# support.net
KiCad netlist of a schematic drawn in Altium Designer
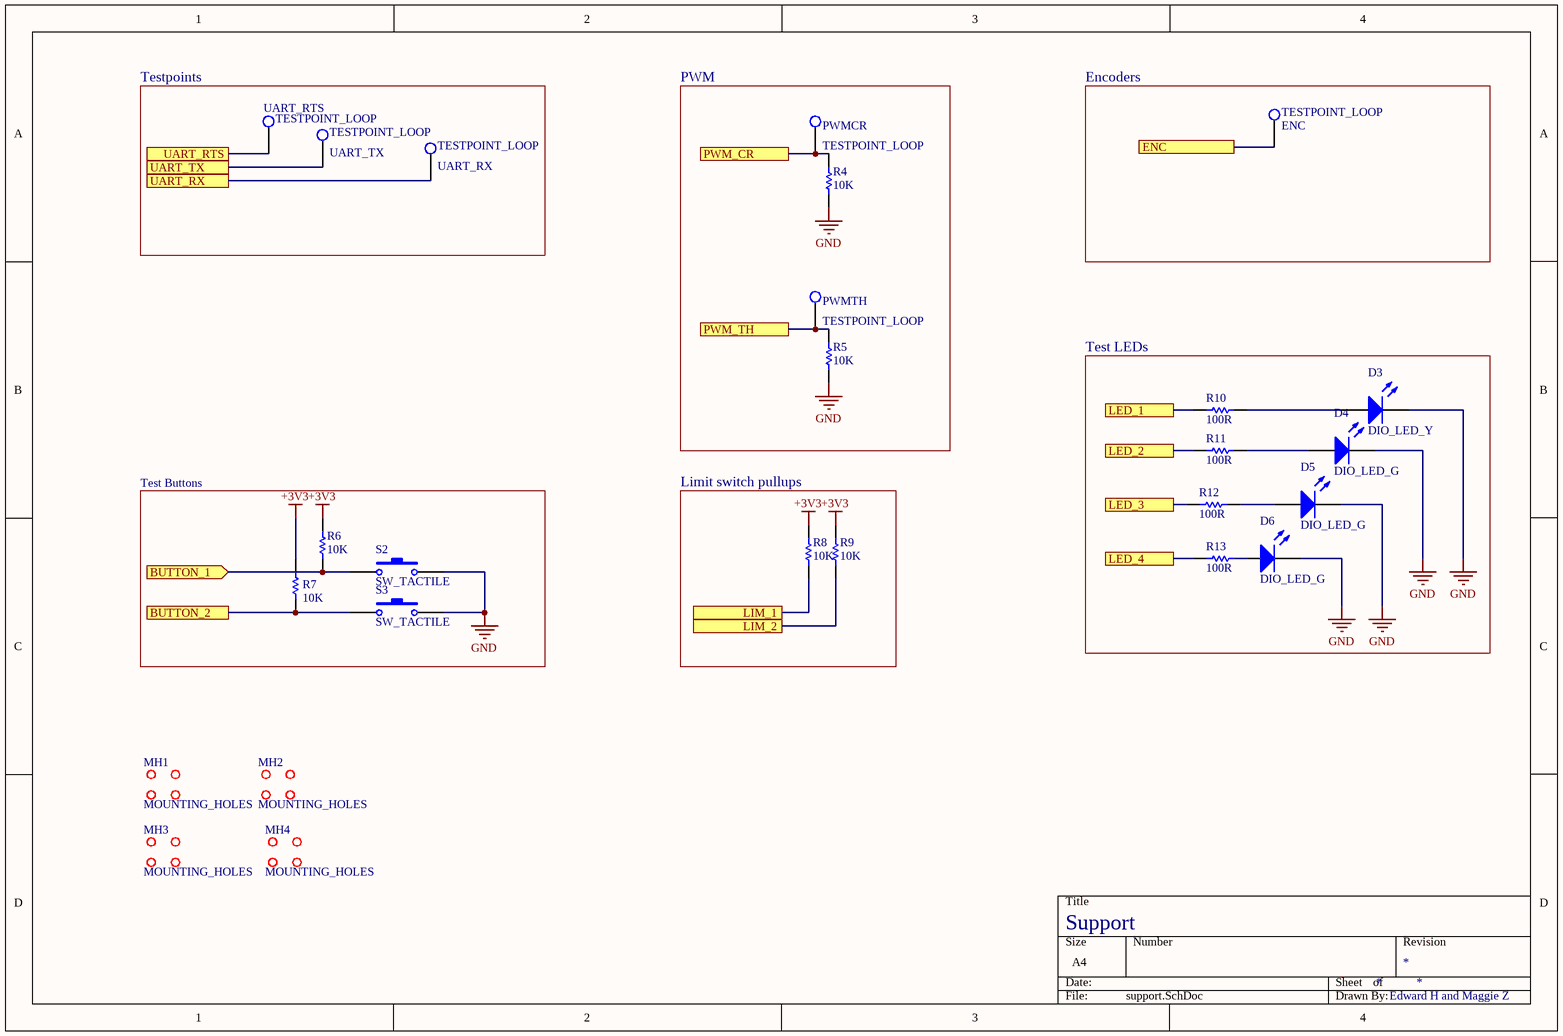
[diagram p0: support.SchDoc]

(export (version "E")
  (design (tool "Eeschema 10.0.6"))
  (components
    (comp (ref "D3")
      (value "DIO_LED_Y")
      (footprint "LED_0805_LINE")
      (description "LED YELLOW DIFFUSED 0805 SMD")
      (fields (field (name "MANUFACTURER") "OSRAM") (field (name "MPN") "LY R976-PS-36"))
      (libsource (lib "UWRT_Schematic_Library_2019") (part "DIO_LED_Y"))
    )
    (comp (ref "D4")
      (value "DIO_LED_G")
      (footprint "LED_0805_LINE")
      (description "LED GREEN DIFFUSED 0805 SMD")
      (fields (field (name "MANUFACTURER") "OSRAM") (field (name "MPN") "LG R971-KN-1"))
      (libsource (lib "UWRT_Schematic_Library_2019") (part "DIO_LED_G"))
    )
    (comp (ref "D5")
      (value "DIO_LED_G")
      (footprint "LED_0805_LINE")
      (description "LED GREEN DIFFUSED 0805 SMD")
      (fields (field (name "MANUFACTURER") "OSRAM") (field (name "MPN") "LG R971-KN-1"))
      (libsource (lib "UWRT_Schematic_Library_2019") (part "DIO_LED_G"))
    )
    (comp (ref "D6")
      (value "DIO_LED_G")
      (footprint "LED_0805_LINE")
      (description "LED GREEN DIFFUSED 0805 SMD")
      (fields (field (name "MANUFACTURER") "OSRAM") (field (name "MPN") "LG R971-KN-1"))
      (libsource (lib "UWRT_Schematic_Library_2019") (part "DIO_LED_G"))
    )
    (comp (ref "ENC")
      (value "TESTPOINT_LOOP")
      (footprint "TESTPOINT_LOOP")
      (libsource (lib "UWRT_Schematic_Library_2019") (part "TESTPOINT_LOOP"))
    )
    (comp (ref "MH1")
      (value "MOUNTING_HOLES")
      (footprint "MOUNTING_HOLE")
      (description "6cm x 6cm")
      (libsource (lib "UWRT_Schematic_Library_2019") (part "MOUNTING_HOLES"))
    )
    (comp (ref "MH2")
      (value "MOUNTING_HOLES")
      (footprint "MOUNTING_HOLE")
      (description "6cm x 6cm")
      (libsource (lib "UWRT_Schematic_Library_2019") (part "MOUNTING_HOLES"))
    )
    (comp (ref "MH3")
      (value "MOUNTING_HOLES")
      (footprint "MOUNTING_HOLE")
      (description "6cm x 6cm")
      (libsource (lib "UWRT_Schematic_Library_2019") (part "MOUNTING_HOLES"))
    )
    (comp (ref "MH4")
      (value "MOUNTING_HOLES")
      (footprint "MOUNTING_HOLE")
      (description "6cm x 6cm")
      (libsource (lib "UWRT_Schematic_Library_2019") (part "MOUNTING_HOLES"))
    )
    (comp (ref "PWMCR")
      (value "TESTPOINT_LOOP")
      (footprint "TESTPOINT_LOOP")
      (libsource (lib "UWRT_Schematic_Library_2019") (part "TESTPOINT_LOOP"))
    )
    (comp (ref "PWMTH")
      (value "TESTPOINT_LOOP")
      (footprint "TESTPOINT_LOOP")
      (libsource (lib "UWRT_Schematic_Library_2019") (part "TESTPOINT_LOOP"))
    )
    (comp (ref "R4")
      (value "10K")
      (footprint "RESC0603(1608)_N")
      (description "RES SMD 10K OHM 5% 1/10W 0603")
      (fields (field (name "MANUFACTURER") "Yageo") (field (name "TOLERANCE") "5%"))
      (libsource (lib "UWRT_Schematic_Library_2019") (part "RES_10K_0603"))
    )
    (comp (ref "R5")
      (value "10K")
      (footprint "RESC0603(1608)_N")
      (description "RES SMD 10K OHM 5% 1/10W 0603")
      (fields (field (name "MANUFACTURER") "Yageo") (field (name "TOLERANCE") "5%"))
      (libsource (lib "UWRT_Schematic_Library_2019") (part "RES_10K_0603"))
    )
    (comp (ref "R6")
      (value "10K")
      (footprint "RESC0603(1608)_N")
      (description "RES SMD 10K OHM 5% 1/10W 0603")
      (fields (field (name "MANUFACTURER") "Yageo") (field (name "TOLERANCE") "5%"))
      (libsource (lib "UWRT_Schematic_Library_2019") (part "RES_10K_0603"))
    )
    (comp (ref "R7")
      (value "10K")
      (footprint "RESC0603(1608)_N")
      (description "RES SMD 10K OHM 5% 1/10W 0603")
      (fields (field (name "MANUFACTURER") "Yageo") (field (name "TOLERANCE") "5%"))
      (libsource (lib "UWRT_Schematic_Library_2019") (part "RES_10K_0603"))
    )
    (comp (ref "R8")
      (value "10K")
      (footprint "RESC0603(1608)_N")
      (description "RES SMD 10K OHM 5% 1/10W 0603")
      (fields (field (name "MANUFACTURER") "Yageo") (field (name "TOLERANCE") "5%"))
      (libsource (lib "UWRT_Schematic_Library_2019") (part "RES_10K_0603"))
    )
    (comp (ref "R9")
      (value "10K")
      (footprint "RESC0603(1608)_N")
      (description "RES SMD 10K OHM 5% 1/10W 0603")
      (fields (field (name "MANUFACTURER") "Yageo") (field (name "TOLERANCE") "5%"))
      (libsource (lib "UWRT_Schematic_Library_2019") (part "RES_10K_0603"))
    )
    (comp (ref "R10")
      (value "100R")
      (footprint "RESC0603(1608)_N")
      (description "RES SMD 100 OHM 1% 1/10W 0603")
      (fields (field (name "MANUFACTURER") "Yageo") (field (name "TOLERANCE") "1%"))
      (libsource (lib "UWRT_Schematic_Library_2019") (part "RES_100R_0603"))
    )
    (comp (ref "R11")
      (value "100R")
      (footprint "RESC0603(1608)_N")
      (description "RES SMD 100 OHM 1% 1/10W 0603")
      (fields (field (name "MANUFACTURER") "Yageo") (field (name "TOLERANCE") "1%"))
      (libsource (lib "UWRT_Schematic_Library_2019") (part "RES_100R_0603"))
    )
    (comp (ref "R12")
      (value "100R")
      (footprint "RESC0603(1608)_N")
      (description "RES SMD 100 OHM 1% 1/10W 0603")
      (fields (field (name "MANUFACTURER") "Yageo") (field (name "TOLERANCE") "1%"))
      (libsource (lib "UWRT_Schematic_Library_2019") (part "RES_100R_0603"))
    )
    (comp (ref "R13")
      (value "100R")
      (footprint "RESC0603(1608)_N")
      (description "RES SMD 100 OHM 1% 1/10W 0603")
      (fields (field (name "MANUFACTURER") "Yageo") (field (name "TOLERANCE") "1%"))
      (libsource (lib "UWRT_Schematic_Library_2019") (part "RES_100R_0603"))
    )
    (comp (ref "S2")
      (value "SW_TACTILE")
      (footprint "B3U-1100P")
      (description "Tactile Switch (Grey)")
      (fields (field (name "DIGIKEY PART NUMBER") "SW1021TR-ND") (field (name "MPN") "B3U-1100P"))
      (libsource (lib "UWRT_Schematic_Library_2019") (part "SW_TACTILE"))
    )
    (comp (ref "S3")
      (value "SW_TACTILE")
      (footprint "B3U-1100P")
      (description "Tactile Switch (Grey)")
      (fields (field (name "DIGIKEY PART NUMBER") "SW1021TR-ND") (field (name "MPN") "B3U-1100P"))
      (libsource (lib "UWRT_Schematic_Library_2019") (part "SW_TACTILE"))
    )
    (comp (ref "UART_RTS")
      (value "TESTPOINT_LOOP")
      (footprint "TESTPOINT_LOOP")
      (libsource (lib "UWRT_Schematic_Library_2019") (part "TESTPOINT_LOOP"))
    )
    (comp (ref "UART_RX")
      (value "TESTPOINT_LOOP")
      (footprint "TESTPOINT_LOOP")
      (libsource (lib "UWRT_Schematic_Library_2019") (part "TESTPOINT_LOOP"))
    )
    (comp (ref "UART_TX")
      (value "TESTPOINT_LOOP")
      (footprint "TESTPOINT_LOOP")
      (libsource (lib "UWRT_Schematic_Library_2019") (part "TESTPOINT_LOOP"))
    )
  )
  (nets
    (net (code "1") (name "+3V3") (class "Default")
      (node (ref "R6") (pin "2") (pinfunction "2_2") (pintype "passive"))
      (node (ref "R7") (pin "1") (pinfunction "1_1") (pintype "passive"))
      (node (ref "R8") (pin "2") (pinfunction "2_2") (pintype "passive"))
      (node (ref "R9") (pin "2") (pinfunction "2_2") (pintype "passive"))
    )
    (net (code "2") (name "/BUTTON_1") (class "Default")
      (node (ref "R6") (pin "1") (pinfunction "1_1") (pintype "passive"))
      (node (ref "S2") (pin "1") (pinfunction "1_1") (pintype "passive"))
    )
    (net (code "3") (name "/BUTTON_2") (class "Default")
      (node (ref "R7") (pin "2") (pinfunction "2_2") (pintype "passive"))
      (node (ref "S3") (pin "1") (pinfunction "1_1") (pintype "passive"))
    )
    (net (code "4") (name "/ENC") (class "Default")
      (node (ref "ENC") (pin "1") (pinfunction "=value_1") (pintype "passive"))
    )
    (net (code "5") (name "/LED_1") (class "Default")
      (node (ref "R10") (pin "2") (pinfunction "2_2") (pintype "passive"))
    )
    (net (code "6") (name "/LED_2") (class "Default")
      (node (ref "R11") (pin "2") (pinfunction "2_2") (pintype "passive"))
    )
    (net (code "7") (name "/LED_3") (class "Default")
      (node (ref "R12") (pin "2") (pinfunction "2_2") (pintype "passive"))
    )
    (net (code "8") (name "/LED_4") (class "Default")
      (node (ref "R13") (pin "2") (pinfunction "2_2") (pintype "passive"))
    )
    (net (code "9") (name "/LIM_1") (class "Default")
      (node (ref "R8") (pin "1") (pinfunction "1_1") (pintype "passive"))
    )
    (net (code "10") (name "/LIM_2") (class "Default")
      (node (ref "R9") (pin "1") (pinfunction "1_1") (pintype "passive"))
    )
    (net (code "11") (name "/PWM_CR") (class "Default")
      (node (ref "PWMCR") (pin "1") (pinfunction "=value_1") (pintype "passive"))
      (node (ref "R4") (pin "2") (pinfunction "2_2") (pintype "passive"))
    )
    (net (code "12") (name "/PWM_TH") (class "Default")
      (node (ref "PWMTH") (pin "1") (pinfunction "=value_1") (pintype "passive"))
      (node (ref "R5") (pin "2") (pinfunction "2_2") (pintype "passive"))
    )
    (net (code "13") (name "/UART_RTS") (class "Default")
      (node (ref "UART_RTS") (pin "1") (pinfunction "=value_1") (pintype "passive"))
    )
    (net (code "14") (name "/UART_RX") (class "Default")
      (node (ref "UART_RX") (pin "1") (pinfunction "=value_1") (pintype "passive"))
    )
    (net (code "15") (name "/UART_TX") (class "Default")
      (node (ref "UART_TX") (pin "1") (pinfunction "=value_1") (pintype "passive"))
    )
    (net (code "16") (name "GND") (class "Default")
      (node (ref "D3") (pin "2") (pinfunction "K_2") (pintype "passive"))
      (node (ref "D4") (pin "2") (pinfunction "K_2") (pintype "passive"))
      (node (ref "D5") (pin "2") (pinfunction "K_2") (pintype "passive"))
      (node (ref "D6") (pin "2") (pinfunction "K_2") (pintype "passive"))
      (node (ref "R4") (pin "1") (pinfunction "1_1") (pintype "passive"))
      (node (ref "R5") (pin "1") (pinfunction "1_1") (pintype "passive"))
      (node (ref "S2") (pin "2") (pinfunction "2_2") (pintype "passive"))
      (node (ref "S3") (pin "2") (pinfunction "2_2") (pintype "passive"))
    )
    (net (code "17") (name "Net-(D3-A)") (class "Default")
      (node (ref "D3") (pin "1") (pinfunction "A_1") (pintype "passive"))
      (node (ref "R10") (pin "1") (pinfunction "1_1") (pintype "passive"))
    )
    (net (code "18") (name "Net-(D4-A)") (class "Default")
      (node (ref "D4") (pin "1") (pinfunction "A_1") (pintype "passive"))
      (node (ref "R11") (pin "1") (pinfunction "1_1") (pintype "passive"))
    )
    (net (code "19") (name "Net-(D5-A)") (class "Default")
      (node (ref "D5") (pin "1") (pinfunction "A_1") (pintype "passive"))
      (node (ref "R12") (pin "1") (pinfunction "1_1") (pintype "passive"))
    )
    (net (code "20") (name "Net-(D6-A)") (class "Default")
      (node (ref "D6") (pin "1") (pinfunction "A_1") (pintype "passive"))
      (node (ref "R13") (pin "1") (pinfunction "1_1") (pintype "passive"))
    )
  )
)
